# Lora_sensor.net
KiCad netlist of a schematic drawn in EAGLE
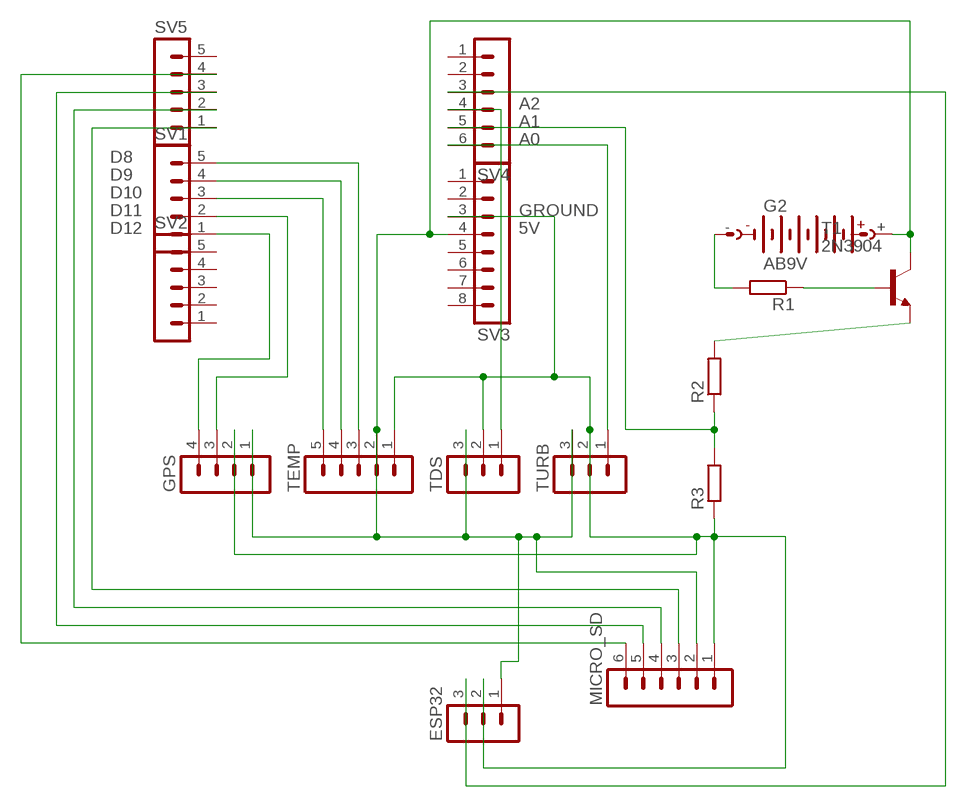
[diagram p0: schematic, sheet 1]

(export (version "E")
  (design (tool "Eeschema 10.0.6"))
  (components
    (comp (ref "ESP32")
      (value "MA03-1")
      (footprint "eagle-import:MA03-1")
      (libsource (lib "eagle-import") (part "MA03-1"))
    )
    (comp (ref "G2")
      (value "AB9V")
      (footprint "eagle-import:AB9V")
      (libsource (lib "eagle-import") (part "AB9V"))
    )
    (comp (ref "GPS")
      (value "MA04-1")
      (footprint "eagle-import:MA04-1")
      (libsource (lib "eagle-import") (part "MA04-1"))
    )
    (comp (ref "MICRO_SD")
      (value "MA06-1")
      (footprint "eagle-import:MA06-1")
      (libsource (lib "eagle-import") (part "MA06-1"))
    )
    (comp (ref "R1")
      (value "R-EU_0204/7")
      (footprint "eagle-import:0204_7")
      (libsource (lib "eagle-import") (part "R-EU_0204/7"))
    )
    (comp (ref "R2")
      (value "R-EU_0204/7")
      (footprint "eagle-import:0204_7")
      (libsource (lib "eagle-import") (part "R-EU_0204/7"))
    )
    (comp (ref "R3")
      (value "R-EU_0204/7")
      (footprint "eagle-import:0204_7")
      (libsource (lib "eagle-import") (part "R-EU_0204/7"))
    )
    (comp (ref "SV1")
      (value "MA05-1")
      (footprint "eagle-import:MA05-1")
      (libsource (lib "eagle-import") (part "MA05-1"))
    )
    (comp (ref "SV2")
      (value "MA05-1")
      (footprint "eagle-import:MA05-1")
      (libsource (lib "eagle-import") (part "MA05-1"))
    )
    (comp (ref "SV3")
      (value "MA08-1")
      (footprint "eagle-import:MA08-1")
      (libsource (lib "eagle-import") (part "MA08-1"))
    )
    (comp (ref "SV4")
      (value "MA06-1")
      (footprint "eagle-import:MA06-1")
      (libsource (lib "eagle-import") (part "MA06-1"))
    )
    (comp (ref "SV5")
      (value "MA05-1")
      (footprint "eagle-import:MA05-1")
      (libsource (lib "eagle-import") (part "MA05-1"))
    )
    (comp (ref "T1")
      (value "2N3904")
      (footprint "eagle-import:TO92")
      (libsource (lib "eagle-import") (part "2N3904"))
    )
    (comp (ref "TDS")
      (value "MA03-1")
      (footprint "eagle-import:MA03-1")
      (libsource (lib "eagle-import") (part "MA03-1"))
    )
    (comp (ref "TEMP")
      (value "MA05-1")
      (footprint "eagle-import:MA05-1")
      (libsource (lib "eagle-import") (part "MA05-1"))
    )
    (comp (ref "TURB")
      (value "MA03-1")
      (footprint "eagle-import:MA03-1")
      (libsource (lib "eagle-import") (part "MA03-1"))
    )
  )
  (nets
    (net (code "1") (name "/5V") (class "Default")
      (node (ref "ESP32") (pin "1") (pinfunction "1_1") (pintype "passive"))
      (node (ref "G2") (pin "+") (pinfunction "+_+") (pintype "passive"))
      (node (ref "GPS") (pin "1") (pinfunction "1_1") (pintype "passive"))
      (node (ref "MICRO_SD") (pin "2") (pinfunction "2_2") (pintype "passive"))
      (node (ref "SV3") (pin "4") (pinfunction "4_4") (pintype "passive"))
      (node (ref "T1") (pin "1") (pinfunction "C_1") (pintype "passive"))
      (node (ref "TDS") (pin "3") (pinfunction "3_3") (pintype "passive"))
      (node (ref "TEMP") (pin "2") (pinfunction "2_2") (pintype "passive"))
      (node (ref "TURB") (pin "3") (pinfunction "3_3") (pintype "passive"))
    )
    (net (code "2") (name "/A0") (class "Default")
      (node (ref "SV4") (pin "6") (pinfunction "6_6") (pintype "passive"))
      (node (ref "TURB") (pin "1") (pinfunction "1_1") (pintype "passive"))
    )
    (net (code "3") (name "/A1") (class "Default")
      (node (ref "R2") (pin "1") (pinfunction "1_1") (pintype "passive"))
      (node (ref "R3") (pin "2") (pinfunction "2_2") (pintype "passive"))
      (node (ref "SV4") (pin "5") (pinfunction "5_5") (pintype "passive"))
    )
    (net (code "4") (name "/A2") (class "Default")
      (node (ref "SV4") (pin "4") (pinfunction "4_4") (pintype "passive"))
      (node (ref "TDS") (pin "1") (pinfunction "1_1") (pintype "passive"))
    )
    (net (code "5") (name "/D8") (class "Default")
      (node (ref "SV1") (pin "5") (pinfunction "5_5") (pintype "passive"))
      (node (ref "TEMP") (pin "3") (pinfunction "3_3") (pintype "passive"))
    )
    (net (code "6") (name "/D9") (class "Default")
      (node (ref "SV1") (pin "4") (pinfunction "4_4") (pintype "passive"))
      (node (ref "TEMP") (pin "4") (pinfunction "4_4") (pintype "passive"))
    )
    (net (code "7") (name "/D10") (class "Default")
      (node (ref "SV1") (pin "3") (pinfunction "3_3") (pintype "passive"))
      (node (ref "TEMP") (pin "5") (pinfunction "5_5") (pintype "passive"))
    )
    (net (code "8") (name "/D11") (class "Default")
      (node (ref "GPS") (pin "3") (pinfunction "3_3") (pintype "passive"))
      (node (ref "SV1") (pin "2") (pinfunction "2_2") (pintype "passive"))
    )
    (net (code "9") (name "/D12") (class "Default")
      (node (ref "GPS") (pin "4") (pinfunction "4_4") (pintype "passive"))
      (node (ref "SV1") (pin "1") (pinfunction "1_1") (pintype "passive"))
    )
    (net (code "10") (name "/GROUND") (class "Default")
      (node (ref "ESP32") (pin "2") (pinfunction "2_2") (pintype "passive"))
      (node (ref "GPS") (pin "2") (pinfunction "2_2") (pintype "passive"))
      (node (ref "MICRO_SD") (pin "1") (pinfunction "1_1") (pintype "passive"))
      (node (ref "R3") (pin "1") (pinfunction "1_1") (pintype "passive"))
      (node (ref "SV3") (pin "3") (pinfunction "3_3") (pintype "passive"))
      (node (ref "TDS") (pin "2") (pinfunction "2_2") (pintype "passive"))
      (node (ref "TEMP") (pin "1") (pinfunction "1_1") (pintype "passive"))
      (node (ref "TURB") (pin "2") (pinfunction "2_2") (pintype "passive"))
    )
    (net (code "11") (name "Net-(ESP32-Pad3)") (class "Default")
      (node (ref "ESP32") (pin "3") (pinfunction "3_3") (pintype "passive"))
      (node (ref "SV4") (pin "3") (pinfunction "3_3") (pintype "passive"))
    )
    (net (code "12") (name "Net-(G2-Pad-)") (class "Default")
      (node (ref "G2") (pin "-") (pinfunction "-_-") (pintype "passive"))
      (node (ref "R1") (pin "2") (pinfunction "2_2") (pintype "passive"))
    )
    (net (code "13") (name "Net-(MICRO_SD-Pad3)") (class "Default")
      (node (ref "MICRO_SD") (pin "3") (pinfunction "3_3") (pintype "passive"))
      (node (ref "SV5") (pin "1") (pinfunction "1_1") (pintype "passive"))
    )
    (net (code "14") (name "Net-(MICRO_SD-Pad4)") (class "Default")
      (node (ref "MICRO_SD") (pin "4") (pinfunction "4_4") (pintype "passive"))
      (node (ref "SV5") (pin "2") (pinfunction "2_2") (pintype "passive"))
    )
    (net (code "15") (name "Net-(MICRO_SD-Pad5)") (class "Default")
      (node (ref "MICRO_SD") (pin "5") (pinfunction "5_5") (pintype "passive"))
      (node (ref "SV5") (pin "3") (pinfunction "3_3") (pintype "passive"))
    )
    (net (code "16") (name "Net-(MICRO_SD-Pad6)") (class "Default")
      (node (ref "MICRO_SD") (pin "6") (pinfunction "6_6") (pintype "passive"))
      (node (ref "SV5") (pin "4") (pinfunction "4_4") (pintype "passive"))
    )
    (net (code "17") (name "Net-(T1-B)") (class "Default")
      (node (ref "R1") (pin "1") (pinfunction "1_1") (pintype "passive"))
      (node (ref "T1") (pin "2") (pinfunction "B_2") (pintype "passive"))
    )
    (net (code "18") (name "Net-(T1-E)") (class "Default")
      (node (ref "R2") (pin "2") (pinfunction "2_2") (pintype "passive"))
      (node (ref "T1") (pin "3") (pinfunction "E_3") (pintype "passive"))
    )
    (net (code "19") (name "unconnected-(SV2-Pad1)") (class "Default")
      (node (ref "SV2") (pin "1") (pinfunction "1_1") (pintype "passive"))
    )
    (net (code "20") (name "unconnected-(SV2-Pad2)") (class "Default")
      (node (ref "SV2") (pin "2") (pinfunction "2_2") (pintype "passive"))
    )
    (net (code "21") (name "unconnected-(SV2-Pad3)") (class "Default")
      (node (ref "SV2") (pin "3") (pinfunction "3_3") (pintype "passive"))
    )
    (net (code "22") (name "unconnected-(SV2-Pad4)") (class "Default")
      (node (ref "SV2") (pin "4") (pinfunction "4_4") (pintype "passive"))
    )
    (net (code "23") (name "unconnected-(SV2-Pad5)") (class "Default")
      (node (ref "SV2") (pin "5") (pinfunction "5_5") (pintype "passive"))
    )
    (net (code "24") (name "unconnected-(SV3-Pad1)") (class "Default")
      (node (ref "SV3") (pin "1") (pinfunction "1_1") (pintype "passive"))
    )
    (net (code "25") (name "unconnected-(SV3-Pad2)") (class "Default")
      (node (ref "SV3") (pin "2") (pinfunction "2_2") (pintype "passive"))
    )
    (net (code "26") (name "unconnected-(SV3-Pad5)") (class "Default")
      (node (ref "SV3") (pin "5") (pinfunction "5_5") (pintype "passive"))
    )
    (net (code "27") (name "unconnected-(SV3-Pad6)") (class "Default")
      (node (ref "SV3") (pin "6") (pinfunction "6_6") (pintype "passive"))
    )
    (net (code "28") (name "unconnected-(SV3-Pad7)") (class "Default")
      (node (ref "SV3") (pin "7") (pinfunction "7_7") (pintype "passive"))
    )
    (net (code "29") (name "unconnected-(SV3-Pad8)") (class "Default")
      (node (ref "SV3") (pin "8") (pinfunction "8_8") (pintype "passive"))
    )
    (net (code "30") (name "unconnected-(SV4-Pad1)") (class "Default")
      (node (ref "SV4") (pin "1") (pinfunction "1_1") (pintype "passive"))
    )
    (net (code "31") (name "unconnected-(SV4-Pad2)") (class "Default")
      (node (ref "SV4") (pin "2") (pinfunction "2_2") (pintype "passive"))
    )
    (net (code "32") (name "unconnected-(SV5-Pad5)") (class "Default")
      (node (ref "SV5") (pin "5") (pinfunction "5_5") (pintype "passive"))
    )
  )
)
